# ina333.net
KiCad netlist of a schematic drawn in EAGLE
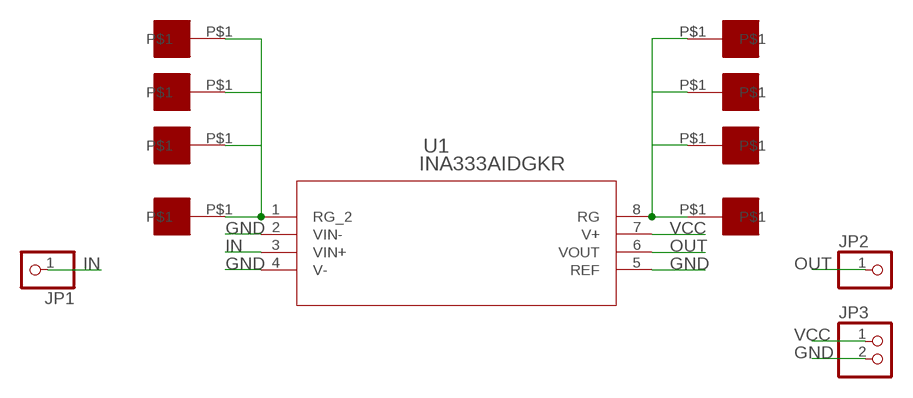
[diagram p0: schematic, sheet 1]

(export (version "E")
  (design (tool "Eeschema 10.0.6"))
  (components
    (comp (ref "JP1")
      (value "PINHD-1X1")
      (footprint "eagle-import:1X01")
      (libsource (lib "eagle-import") (part "PINHD-1X1"))
    )
    (comp (ref "JP2")
      (value "PINHD-1X1")
      (footprint "eagle-import:1X01")
      (libsource (lib "eagle-import") (part "PINHD-1X1"))
    )
    (comp (ref "JP3")
      (value "PINHD-1X2")
      (footprint "eagle-import:1X02")
      (libsource (lib "eagle-import") (part "PINHD-1X2"))
    )
    (comp (ref "U$1")
      (value "PAD")
      (footprint "eagle-import:PAD")
      (libsource (lib "eagle-import") (part "PAD"))
    )
    (comp (ref "U$2")
      (value "PAD")
      (footprint "eagle-import:PAD")
      (libsource (lib "eagle-import") (part "PAD"))
    )
    (comp (ref "U$3")
      (value "PAD")
      (footprint "eagle-import:PAD")
      (libsource (lib "eagle-import") (part "PAD"))
    )
    (comp (ref "U$4")
      (value "PAD")
      (footprint "eagle-import:PAD")
      (libsource (lib "eagle-import") (part "PAD"))
    )
    (comp (ref "U$5")
      (value "PAD")
      (footprint "eagle-import:PAD")
      (libsource (lib "eagle-import") (part "PAD"))
    )
    (comp (ref "U$6")
      (value "PAD")
      (footprint "eagle-import:PAD")
      (libsource (lib "eagle-import") (part "PAD"))
    )
    (comp (ref "U$7")
      (value "PAD")
      (footprint "eagle-import:PAD")
      (libsource (lib "eagle-import") (part "PAD"))
    )
    (comp (ref "U$8")
      (value "PAD")
      (footprint "eagle-import:PAD")
      (libsource (lib "eagle-import") (part "PAD"))
    )
    (comp (ref "U1")
      (value "INA333AIDGKR")
      (footprint "eagle-import:DGK8")
      (libsource (lib "eagle-import") (part "INA333AIDGKR"))
    )
  )
  (nets
    (net (code "1") (name "/GND") (class "Default")
      (node (ref "JP3") (pin "2") (pinfunction "2_2") (pintype "passive"))
      (node (ref "U1") (pin "2") (pinfunction "VIN-_2") (pintype "input"))
      (node (ref "U1") (pin "4") (pinfunction "V-_4") (pintype "power_in"))
      (node (ref "U1") (pin "5") (pinfunction "REF_5") (pintype "passive"))
    )
    (net (code "2") (name "/IN") (class "Default")
      (node (ref "JP1") (pin "1") (pinfunction "1_1") (pintype "passive"))
      (node (ref "U1") (pin "3") (pinfunction "VIN+_3") (pintype "input"))
    )
    (net (code "3") (name "/OUT") (class "Default")
      (node (ref "JP2") (pin "1") (pinfunction "1_1") (pintype "passive"))
      (node (ref "U1") (pin "6") (pinfunction "VOUT_6") (pintype "output"))
    )
    (net (code "4") (name "/VCC") (class "Default")
      (node (ref "JP3") (pin "1") (pinfunction "1_1") (pintype "passive"))
      (node (ref "U1") (pin "7") (pinfunction "V+_7") (pintype "power_in"))
    )
    (net (code "5") (name "Net-(U1-RG)") (class "Default")
      (node (ref "U$2") (pin "P$1") (pinfunction "P$1_P$1") (pintype "bidirectional"))
      (node (ref "U$4") (pin "P$1") (pinfunction "P$1_P$1") (pintype "bidirectional"))
      (node (ref "U$7") (pin "P$1") (pinfunction "P$1_P$1") (pintype "bidirectional"))
      (node (ref "U$8") (pin "P$1") (pinfunction "P$1_P$1") (pintype "bidirectional"))
      (node (ref "U1") (pin "8") (pinfunction "RG_8") (pintype "passive"))
    )
    (net (code "6") (name "Net-(U1-RG_2)") (class "Default")
      (node (ref "U$1") (pin "P$1") (pinfunction "P$1_P$1") (pintype "bidirectional"))
      (node (ref "U$3") (pin "P$1") (pinfunction "P$1_P$1") (pintype "bidirectional"))
      (node (ref "U$5") (pin "P$1") (pinfunction "P$1_P$1") (pintype "bidirectional"))
      (node (ref "U$6") (pin "P$1") (pinfunction "P$1_P$1") (pintype "bidirectional"))
      (node (ref "U1") (pin "1") (pinfunction "RG_2_1") (pintype "passive"))
    )
  )
)
